# PowerSupply.net
KiCad netlist of a schematic drawn in Altium Designer
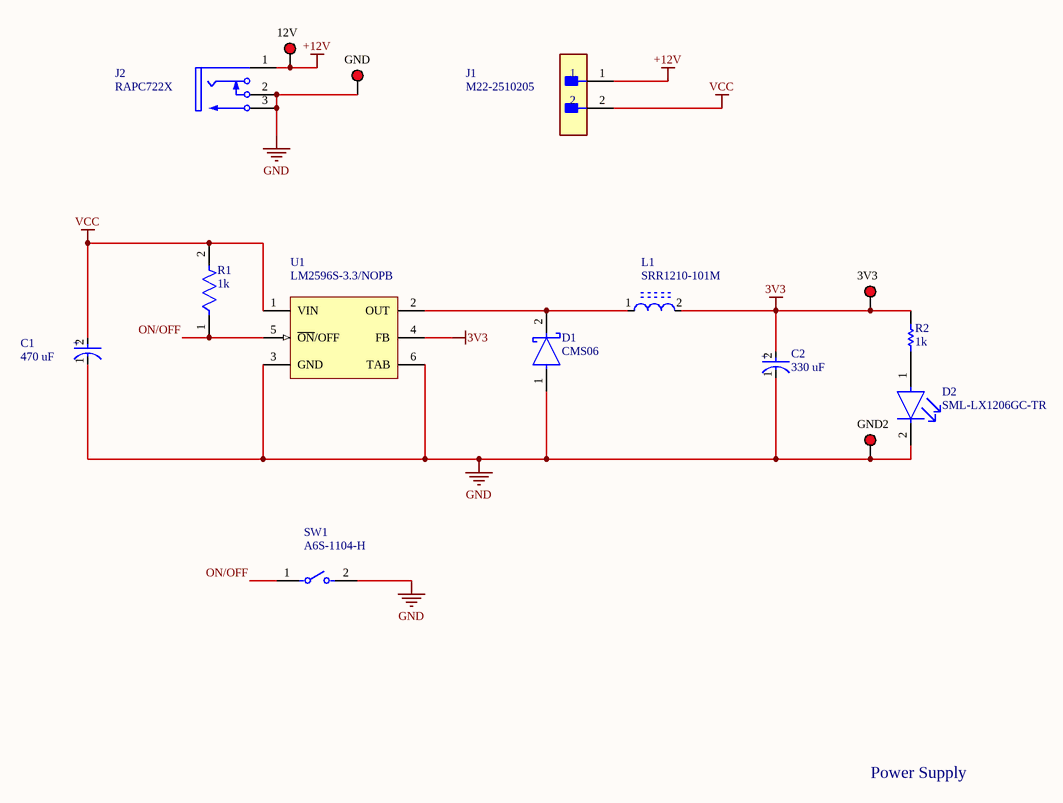
[diagram p0: PowerSupply.SchDoc]

(export (version "E")
  (design (tool "Eeschema 10.0.6"))
  (components
    (comp (ref "3V3")
      (value "5010")
      (footprint "KSTN-5010_V")
      (description "Test Point, Red, Through Hole, RoHS, Bulk")
      (fields (field (name "MANUFACTURER") "Keystone"))
      (libsource (lib "Altium Content Vault") (part "TESTPOINT_RED"))
    )
    (comp (ref "12V")
      (value "5010")
      (footprint "KSTN-5010_V")
      (description "Test Point, Red, Through Hole, RoHS, Bulk")
      (fields (field (name "MANUFACTURER") "Keystone"))
      (libsource (lib "Altium Content Vault") (part "TESTPOINT_RED"))
    )
    (comp (ref "C1")
      (value "470 uF")
      (footprint "FP-FKF-MFG")
      (description "CAP ALUM 100UF 20% 50V SMD")
      (fields (field (name "VOLTAGE") "50V") (field (name "TOLERANCE") "20%"))
      (libsource (lib "Altium Content Vault") (part "a00bbbee19879c290e62620ae7e47b1"))
    )
    (comp (ref "C2")
      (value "330 uF")
      (footprint "FP-FKG-MFG")
      (description "CAP ALUM 330UF 20% 35V SMD")
      (fields (field (name "VOLTAGE") "35V") (field (name "TOLERANCE") "20%"))
      (libsource (lib "Altium Content Vault") (part "203bc49f2ac43e59fd269a8c329ed05"))
    )
    (comp (ref "D1")
      (value "CMS06")
      (footprint "FP-M-FLAT-MFG")
      (description "DIODE SCHOTTKY 30V 2A MFLAT")
      (libsource (lib "Altium Content Vault") (part "360ad2f4ac25a952324d13796385471"))
    )
    (comp (ref "D2")
      (value "SML-LX1206GC-TR")
      (footprint "FP-SML-LX1206GC-TR-MFG")
      (description "LED GREEN CLEAR 1206 SMD")
      (libsource (lib "Altium Content Vault") (part "ab1c01a81903e929fc6c44469aada92"))
    )
    (comp (ref "GND")
      (value "5010")
      (footprint "KSTN-5010_V")
      (description "Test Point, Red, Through Hole, RoHS, Bulk")
      (fields (field (name "MANUFACTURER") "Keystone"))
      (libsource (lib "Altium Content Vault") (part "TESTPOINT_RED"))
    )
    (comp (ref "GND2")
      (value "5010")
      (footprint "KSTN-5010_V")
      (description "Test Point, Red, Through Hole, RoHS, Bulk")
      (fields (field (name "MANUFACTURER") "Keystone"))
      (libsource (lib "Altium Content Vault") (part "TESTPOINT_RED"))
    )
    (comp (ref "J1")
      (value "M22-2510205")
      (footprint "FP-M22-2510205-MFG")
      (description "CONN HEADER VERT 2POS 2MM")
      (fields
        (field (name "MANUFACTURER") "Harwin")
        (field (name "OCTOPART") "https://octopart.com/m22-2510205-harwin-2538221")
      )
      (libsource (lib "Altium Content Vault") (part "3bc925449376181038e59eaffc5286c"))
    )
    (comp (ref "J2")
      (value "RAPC722X")
      (footprint "SWITCH-RAPC712X-3_V")
      (description "Power Jack, 5 A, 3-Pin THD, RoHS, Bulk")
      (fields (field (name "MANUFACTURER") "Switchcraft"))
      (libsource (lib "Altium Content Vault") (part "SWITCH-RAPC712X-3"))
    )
    (comp (ref "L1")
      (value "SRR1210-101M")
      (footprint "FP-SRR1210-MFG")
      (description "FIXED IND 100UH 2.5A 135MOHM SMD")
      (fields (field (name "TOLERANCE") "20%"))
      (libsource (lib "Altium Content Vault") (part "b0910935bcc1a60cf5c5c74d6a451c2"))
    )
    (comp (ref "R1")
      (value "1k")
      (footprint "FP-CRCW1206-e3-MFG")
      (description "RES Thick Film, 1.2kΩ, 1%, 0.25W, 100ppm/°C, 1206")
      (fields (field (name "TOLERANCE") "1%"))
      (libsource (lib "Altium Content Vault") (part "1029c3af85768c4190bb7ad29bc67b5"))
    )
    (comp (ref "R2")
      (value "1k")
      (footprint "RESC3216X70X50ML20T25")
      (fields (field (name "PART NUMBER") "ERA8AEB202V") (field (name "MANUFACTURER") "Panasonic"))
      (libsource (lib "Altium Content Vault") (part "RES"))
    )
    (comp (ref "SW1")
      (value "A6S-1104-H")
      (footprint "FP-A6S-1104-H-MFG")
      (description "SWITCH SLIDE DIP SPST 25MA 24V")
      (fields
        (field (name "MANUFACTURER") "Omron Electronics Inc-EMC Div")
        (field (name "OCTOPART") "https://octopart.com/a6s-1104-h-omron-55410938")
      )
      (libsource (lib "Altium Content Vault") (part "bb27bde45df87f1f469753f287ef5ae"))
    )
    (comp (ref "U1")
      (value "LM2596S-3.3/NOPB")
      (footprint "KTT0005B_M")
      (description "SIMPLE SWITCHER® Power Converter 150 KHz 3A Step-Down Voltage Regulator, 5-pin TO-263, Pb-Free")
      (fields (field (name "MANUFACTURER") "Texas Instruments"))
      (libsource (lib "Altium Content Vault") (part "PM-REG-LM2575HVS-12"))
    )
  )
  (nets
    (net (code "1") (name "+12V") (class "Default")
      (node (ref "12V") (pin "1") (pinfunction "1_1") (pintype "passive"))
      (node (ref "J1") (pin "1") (pinfunction "1_1") (pintype "passive"))
      (node (ref "J2") (pin "1") (pinfunction "1_1") (pintype "passive"))
    )
    (net (code "2") (name "/ON{slash}OFF") (class "Default")
      (node (ref "R1") (pin "1") (pinfunction "1_1") (pintype "passive"))
      (node (ref "SW1") (pin "1") (pinfunction "1_1") (pintype "passive"))
      (node (ref "U1") (pin "5") (pinfunction "~{ON}/OFF_5") (pintype "input"))
    )
    (net (code "3") (name "3V3") (class "Default")
      (node (ref "3V3") (pin "1") (pinfunction "1_1") (pintype "passive"))
      (node (ref "C2") (pin "2") (pinfunction "A_2") (pintype "passive"))
      (node (ref "L1") (pin "2") (pinfunction "2_2") (pintype "passive"))
      (node (ref "R2") (pin "2") (pinfunction "2_2") (pintype "passive"))
      (node (ref "U1") (pin "4") (pinfunction "FB_4") (pintype "power_in"))
    )
    (net (code "4") (name "GND") (class "Default")
      (node (ref "C1") (pin "1") (pinfunction "C_1") (pintype "passive"))
      (node (ref "C2") (pin "1") (pinfunction "C_1") (pintype "passive"))
      (node (ref "D1") (pin "1") (pinfunction "A_1") (pintype "passive"))
      (node (ref "D2") (pin "2") (pinfunction "C_2") (pintype "passive"))
      (node (ref "GND") (pin "1") (pinfunction "1_1") (pintype "passive"))
      (node (ref "GND2") (pin "1") (pinfunction "1_1") (pintype "passive"))
      (node (ref "J2") (pin "2") (pinfunction "2_2") (pintype "passive"))
      (node (ref "J2") (pin "3") (pinfunction "3_3") (pintype "passive"))
      (node (ref "SW1") (pin "2") (pinfunction "2_2") (pintype "passive"))
      (node (ref "U1") (pin "3") (pinfunction "GND_3") (pintype "power_in"))
      (node (ref "U1") (pin "6") (pinfunction "TAB_6") (pintype "power_in"))
    )
    (net (code "5") (name "Net-(D1-C)") (class "Default")
      (node (ref "D1") (pin "2") (pinfunction "C_2") (pintype "passive"))
      (node (ref "L1") (pin "1") (pinfunction "1_1") (pintype "passive"))
      (node (ref "U1") (pin "2") (pinfunction "OUT_2") (pintype "power_in"))
    )
    (net (code "6") (name "Net-(D2-A)") (class "Default")
      (node (ref "D2") (pin "1") (pinfunction "A_1") (pintype "passive"))
      (node (ref "R2") (pin "1") (pinfunction "1_1") (pintype "passive"))
    )
    (net (code "7") (name "VCC") (class "Default")
      (node (ref "C1") (pin "2") (pinfunction "A_2") (pintype "passive"))
      (node (ref "J1") (pin "2") (pinfunction "2_2") (pintype "passive"))
      (node (ref "R1") (pin "2") (pinfunction "2_2") (pintype "passive"))
      (node (ref "U1") (pin "1") (pinfunction "VIN_1") (pintype "power_in"))
    )
  )
)
